# Power_Management.net
KiCad netlist of a schematic drawn in Altium Designer
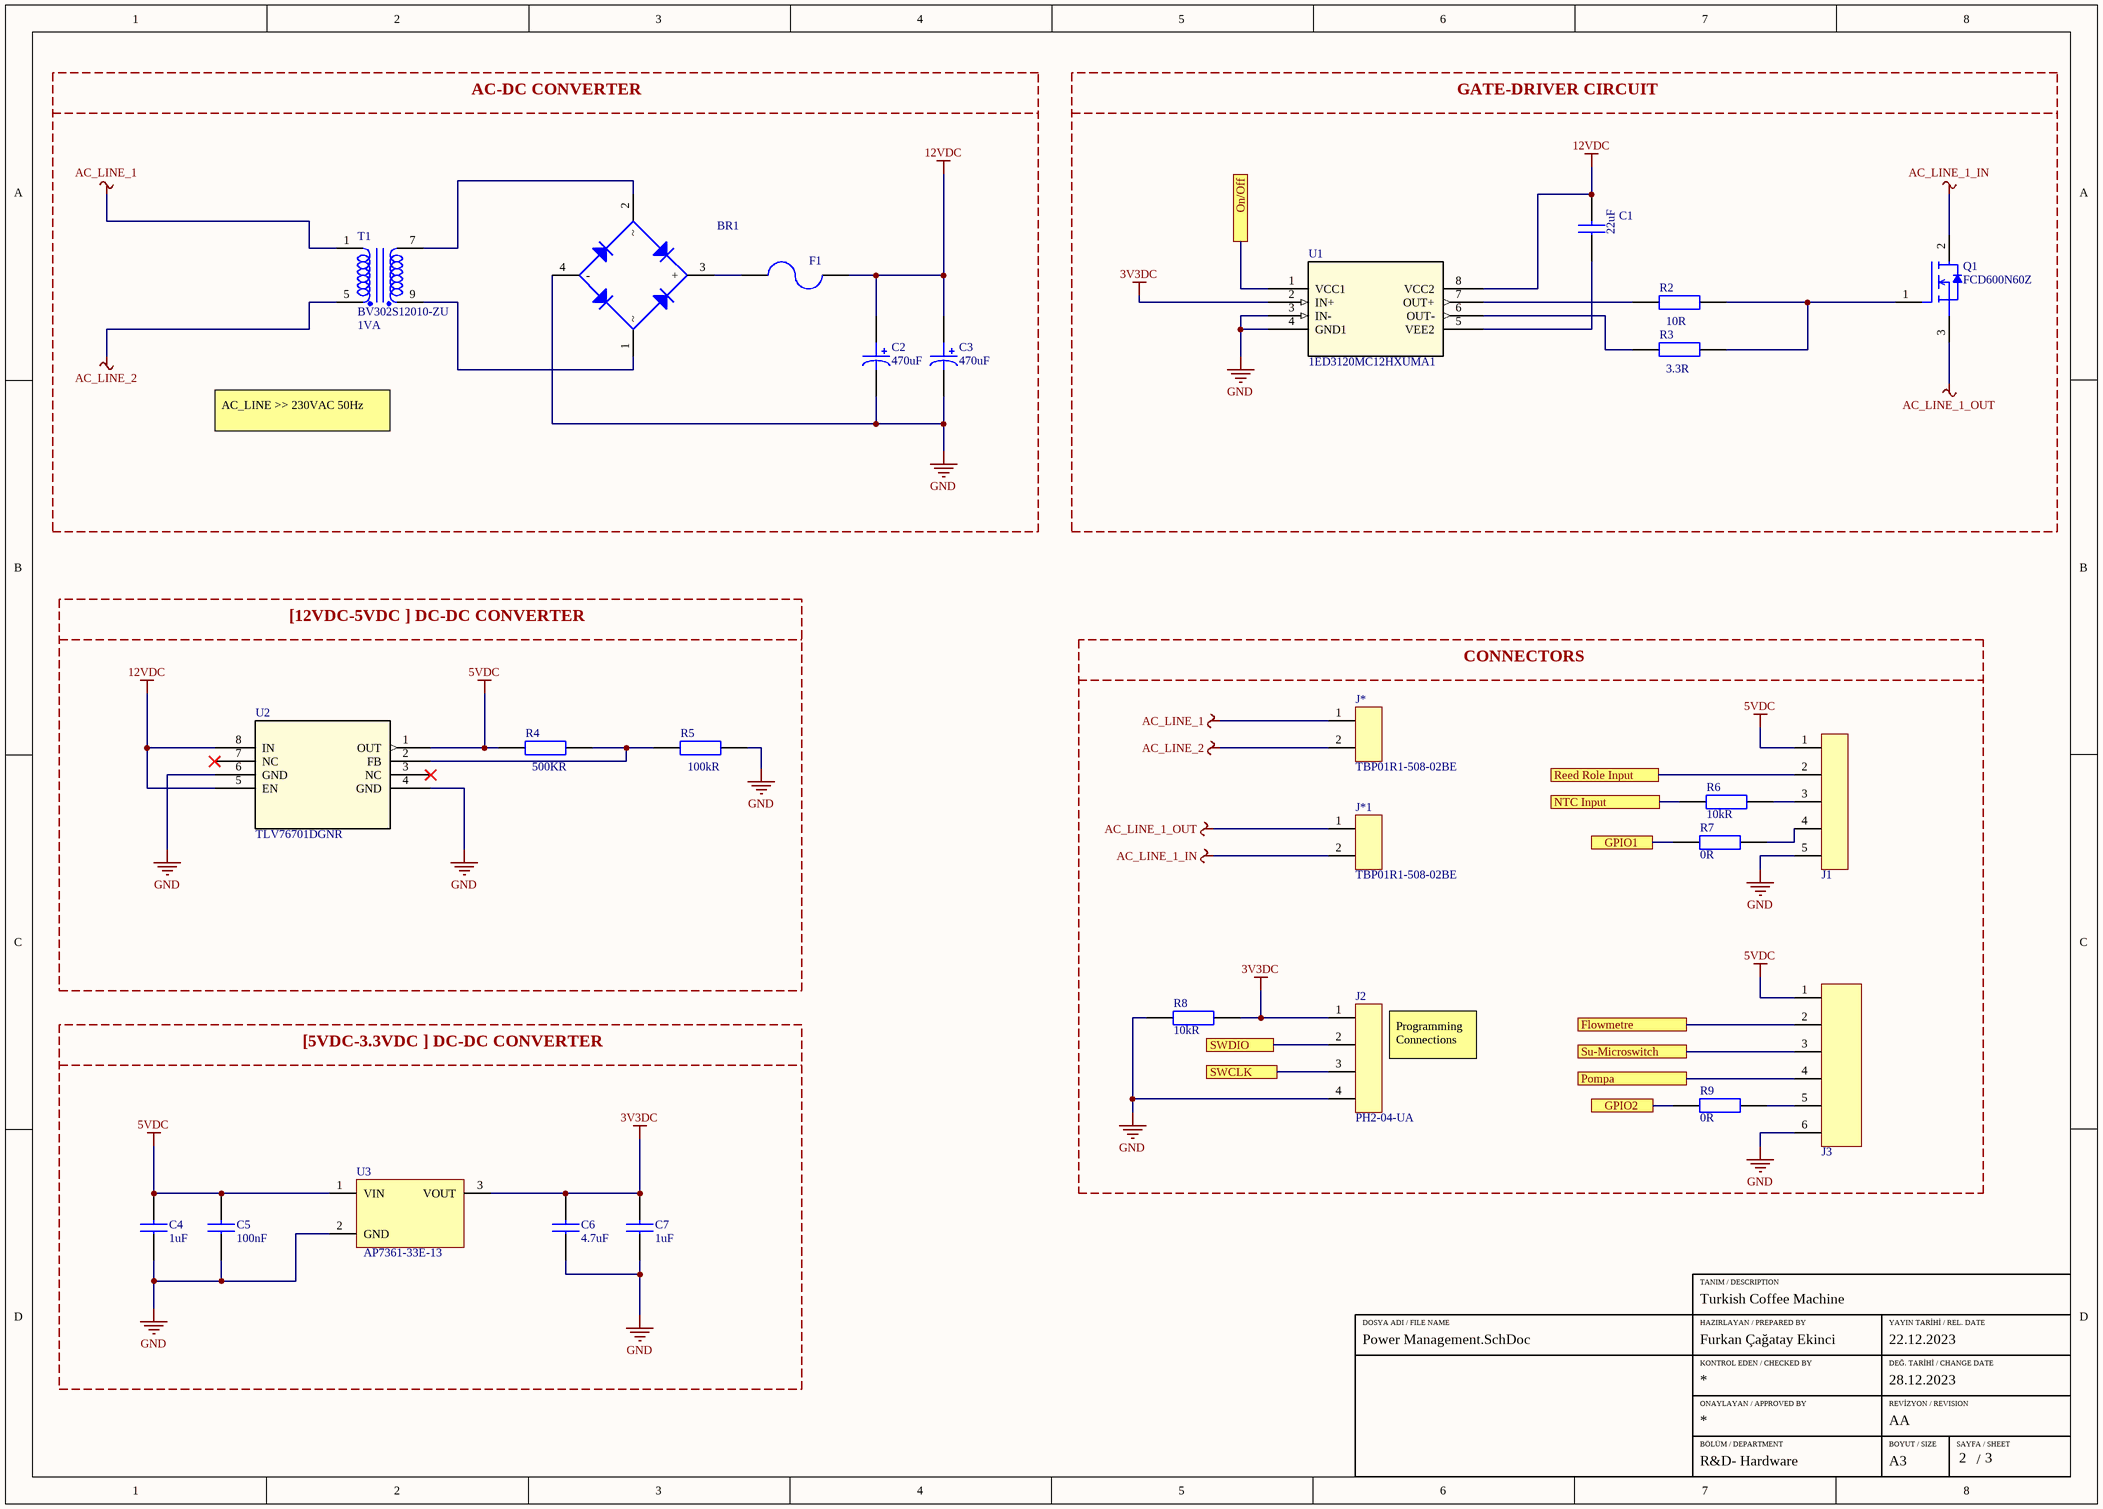
[diagram p0: Power Management.SchDoc]

(export (version "E")
  (design (tool "Eeschema 10.0.6"))
  (components
    (comp (ref "BR1")
      (value "DB105STR")
      (footprint "DB105STR")
      (description "Bridge Diode AC-DC")
      (fields (field (name "MANUFACTURER") "Sangdest Microelectronics") (field (name "DESIGNED BY") "FCE"))
      (libsource (lib "Coffee Machine") (part "DB105STR"))
    )
    (comp (ref "C1")
      (value "CL10A226MO7JZNC")
      (footprint "CAP_0603")
      (description "Multilayer Ceramic Capacitor, 22 uF, 16 V, ± 20%, X5R, 0603 [1608 Metric]")
      (fields
        (field (name "MANUFACTURER") "Samsung")
        (field (name "TOLERANCE") "20%")
        (field (name "DESIGNED BY") "FCE")
      )
      (libsource (lib "Coffee Machine") (part "CAP CER 22uF 0603"))
    )
    (comp (ref "C2")
      (value "ESH477M050AH4AA")
      (footprint "CAP_RADIAL_D10_P5")
      (description "CAP ALU ELEC 470uF 50V RADIAL")
      (fields
        (field (name "MANUFACTURER") "KEMET")
        (field (name "TOLERANCE") "20%")
        (field (name "CAPACITANCE") "470uF")
        (field (name "DESIGNED BY") "FCE")
      )
      (libsource (lib "Coffee Machine") (part "CAP ALU ELEC 470uF 50V"))
    )
    (comp (ref "C3")
      (value "ESH477M050AH4AA")
      (footprint "CAP_RADIAL_D10_P5")
      (description "CAP ALU ELEC 470uF 50V RADIAL")
      (fields
        (field (name "MANUFACTURER") "KEMET")
        (field (name "TOLERANCE") "20%")
        (field (name "CAPACITANCE") "470uF")
        (field (name "DESIGNED BY") "FCE")
      )
      (libsource (lib "Coffee Machine") (part "CAP ALU ELEC 470uF 50V"))
    )
    (comp (ref "C4")
      (value "CL21B105KBFNNNE")
      (footprint "CAP_0805")
      (description "CAP CER 1uF %10 0805")
      (fields
        (field (name "MANUFACTURER") "Samsung")
        (field (name "TOLERANCE") "10%")
        (field (name "CAPACITANCE") "1uF")
        (field (name "DESIGNED BY") "FCE")
      )
      (libsource (lib "Coffee Machine") (part "CAP CER 1uF 0805"))
    )
    (comp (ref "C5")
      (value "C0603C104K5RACTU")
      (footprint "CAP_0603")
      (description "CAP CER 100nF %10 0603 SMD")
      (fields
        (field (name "MANUFACTURER") "KEMET")
        (field (name "TOLERANCE") "10%")
        (field (name "CAPACITANCE") "100nF")
        (field (name "DESIGNED BY") "FCE")
      )
      (libsource (lib "Coffee Machine") (part "CAP CER 100nF 0603"))
    )
    (comp (ref "C6")
      (value "CL21A475KAQNNNE")
      (footprint "CAP_0805")
      (description "CAP CER 4.7uF %10 0805")
      (fields
        (field (name "MANUFACTURER") "Samsung")
        (field (name "TOLERANCE") "10%")
        (field (name "CAPACITANCE") "4.7uF")
        (field (name "DESIGNED BY") "FCE")
      )
      (libsource (lib "Coffee Machine") (part "CAP CER 4.7uF 0805"))
    )
    (comp (ref "C7")
      (value "CL21B105KBFNNNE")
      (footprint "CAP_0805")
      (description "CAP CER 1uF %10 0805")
      (fields
        (field (name "MANUFACTURER") "Samsung")
        (field (name "TOLERANCE") "10%")
        (field (name "CAPACITANCE") "1uF")
        (field (name "DESIGNED BY") "FCE")
      )
      (libsource (lib "Coffee Machine") (part "CAP CER 1uF 0805"))
    )
    (comp (ref "F1")
      (value "3413.0216.22")
      (footprint "3413.0216.22")
      (description "FUSE BRD MNT 1A 32VAC 63VDC 1206")
      (fields (field (name "MANUFACTURER") "Schurter") (field (name "DESIGNED BY") "FCE"))
      (libsource (lib "Coffee Machine") (part "FUSE 3413.0216.22"))
    )
    (comp (ref "J*")
      (value "TBP01R1-508-02BE")
      (footprint "TBP01R1-508")
      (description "2~24 Poles, Pluggable, Receptacle, Horizontal, 5.08 Pitch, Terminal Block Connector")
      (fields
        (field (name "MANUFACTURER") "CUI Devices")
        (field (name "VOLTAGE") "300V")
        (field (name "DESIGNED BY") "FCE")
      )
      (libsource (lib "Coffee Machine") (part "TBP01R1-508-02BE"))
    )
    (comp (ref "J*1")
      (value "TBP01R1-508-02BE")
      (footprint "TBP01R1-508")
      (description "2~24 Poles, Pluggable, Receptacle, Horizontal, 5.08 Pitch, Terminal Block Connector")
      (fields
        (field (name "MANUFACTURER") "CUI Devices")
        (field (name "VOLTAGE") "300V")
        (field (name "DESIGNED BY") "FCE")
      )
      (libsource (lib "Coffee Machine") (part "TBP01R1-508-02BE"))
    )
    (comp (ref "J1")
      (value "SMH-105-02-L-S")
      (footprint "PINHEADER1X5_RA")
      (description ".100 C.L. HORIZONTAL SMT SOCKET")
      (fields (field (name "MANUFACTURER") "Samtec") (field (name "DESIGNED BY") "FCE"))
      (libsource (lib "Coffee Machine") (part "SMH-105-02-L-S"))
    )
    (comp (ref "J2")
      (value "PH2-04-UA")
      (footprint "BULK")
      (description "Conn Unshrouded Header HDR 4 POS 2.54mm Solder ST Thru-Hole")
      (fields (field (name "MANUFACTURER") "Adam Equipment") (field (name "DESIGNED BY") "FCE"))
      (libsource (lib "Coffee Machine") (part "PH2-04-UA"))
    )
    (comp (ref "J3")
      (value "64800611622")
      (footprint "64800611622")
      (description "1.50mm 6PIN Connector")
      (fields (field (name "MANUFACTURER") "Wurth Electronics") (field (name "DESIGNED BY") "FCE"))
      (libsource (lib "Coffee Machine") (part "64800611622_conn_6pin"))
    )
    (comp (ref "Q1")
      (value "FCD600N60Z")
      (footprint "DPAK_TO-252AA_INF")
      (description "N-Channel Power MOSFET, SUPERFET® II, FAST, 600 V, 7.4 A, 600 mΩ, DPAK")
      (fields (field (name "MANUFACTURER") "ON Semiconductor / Fairchild") (field (name "DESIGNED BY") "FCE"))
      (libsource (lib "Coffee Machine") (part "FCD600N60Z"))
    )
    (comp (ref "R2")
      (value "RC0603FR-0710RL")
      (footprint "RES_0603")
      (description "SMD Chip Resistor, 10 Ohm, ± 1%, 100 mW, 0603 [1608 Metric], Thick Film, General Purpose")
      (fields
        (field (name "MANUFACTURER") "Yageo")
        (field (name "TOLERANCE") "1%")
        (field (name "DESIGNED BY") "FCE")
      )
      (libsource (lib "Coffee Machine") (part "RES 10 OHM 0603"))
    )
    (comp (ref "R3")
      (value "RC0603JR-073R3L")
      (footprint "RES_0603")
      (description "Res Thick Film 0603 3.3 Ohm 5% 1/10W +/-200ppm/ßC Molded SMD Paper T/R")
      (fields
        (field (name "MANUFACTURER") "Yageo")
        (field (name "TOLERANCE") "5%")
        (field (name "DESIGNED BY") "FCE")
      )
      (libsource (lib "Coffee Machine") (part "RES 3.3 OHM 0603"))
    )
    (comp (ref "R4")
      (value "CRMA1206AF500KFKEF")
      (footprint "RES_1206")
      (description "Res Thick Film 1206 500K Ohm 1% 0.3W ±100ppm/C Pad SMD Automotive T/R")
      (fields
        (field (name "MANUFACTURER") "Vishay BCcomponents")
        (field (name "TOLERANCE") "1%")
        (field (name "DESIGNED BY") "FCE")
      )
      (libsource (lib "Coffee Machine") (part "RES 500K OHM 0603"))
    )
    (comp (ref "R5")
      (value "RC0603JR-07100KL")
      (footprint "RES_0603")
      (description "SMD Chip Resistor, 100 kOhm, ± 5%, 100 mW, 0603 [1608 Metric], Thick Film, General Purpose")
      (fields
        (field (name "MANUFACTURER") "Yageo")
        (field (name "TOLERANCE") "5%")
        (field (name "DESIGNED BY") "FCE")
      )
      (libsource (lib "Coffee Machine") (part "RES 100K OHM 0603"))
    )
    (comp (ref "R6")
      (value "RC0603FR-0710KL")
      (footprint "RES_0603")
      (description "RES 10K %1 OHM 0603 SMD")
      (fields
        (field (name "MANUFACTURER") "Yageo")
        (field (name "TOLERANCE") "1%")
        (field (name "RESISTANCE") "10kR")
        (field (name "DESIGNED BY") "FCE")
      )
      (libsource (lib "Coffee Machine") (part "RES 10K OHM 0603"))
    )
    (comp (ref "R7")
      (value "RC0603JR-070RL")
      (footprint "RES_0603")
      (description "RES 0 %1 OHM 0603 SMD")
      (fields
        (field (name "MANUFACTURER") "Yageo")
        (field (name "TOLERANCE") "1%")
        (field (name "RESISTANCE") "0R")
        (field (name "DESIGNED BY") "FCE")
      )
      (libsource (lib "Coffee Machine") (part "RES 0 OHM 0603"))
    )
    (comp (ref "R8")
      (value "RC0603FR-0710KL")
      (footprint "RES_0603")
      (description "RES 10K %1 OHM 0603 SMD")
      (fields
        (field (name "MANUFACTURER") "Yageo")
        (field (name "TOLERANCE") "1%")
        (field (name "RESISTANCE") "10kR")
        (field (name "DESIGNED BY") "FCE")
      )
      (libsource (lib "Coffee Machine") (part "RES 10K OHM 0603"))
    )
    (comp (ref "R9")
      (value "RC0603JR-070RL")
      (footprint "RES_0603")
      (description "RES 0 %1 OHM 0603 SMD")
      (fields
        (field (name "MANUFACTURER") "Yageo")
        (field (name "TOLERANCE") "1%")
        (field (name "RESISTANCE") "0R")
        (field (name "DESIGNED BY") "FCE")
      )
      (libsource (lib "Coffee Machine") (part "RES 0 OHM 0603"))
    )
    (comp (ref "T1")
      (value "BV302S12010-ZU")
      (footprint "BV302S")
      (description "230-12 Transformer 1VA")
      (fields
        (field (name "MANUFACTURER") "Zettler Magnetics")
        (field (name "RATED POWER") "1VA")
        (field (name "DESIGNED BY") "FCE")
      )
      (libsource (lib "Coffee Machine") (part "BV302S12010-ZU"))
    )
    (comp (ref "U1")
      (value "1ED3120MC12HXUMA1")
      (footprint "SOIC8")
      (description "IGBT & MOSFET Gate Driver 5.5A 1-OUT Hi Side Non-Inv/Inv 8-Pin DSO T/R")
      (fields (field (name "MANUFACTURER") "Infineon") (field (name "DESIGNED BY") "FCE"))
      (libsource (lib "Coffee Machine") (part "1ED3120MC12HXUMA1"))
    )
    (comp (ref "U2")
      (value "TLV76701DGNR")
      (footprint "PG-DSO-8-66")
      (fields (field (name "MANUFACTURER") "Texas Instruments") (field (name "DESIGNED BY") "FCE"))
      (libsource (lib "Coffee Machine") (part "TLV76701DGNR"))
    )
    (comp (ref "U3")
      (value "AP7361-33E-13")
      (footprint "SOT223")
      (description "LDO Regulator Pos 3.3V 1A 4-Pin(3+Tab) SOT-223 T/R")
      (fields (field (name "MANUFACTURER") "Diodes") (field (name "DESIGNED BY") "FCE"))
      (libsource (lib "Coffee Machine") (part "AP7361-33E-13"))
    )
  )
  (nets
    (net (code "1") (name "/Flowmetre") (class "Default") (node (ref "J3") (pin "2") (pintype "power_in")))
    (net (code "2") (name "/GPIO1") (class "Default")
      (node (ref "R7") (pin "1") (pinfunction "1_1") (pintype "passive"))
    )
    (net (code "3") (name "/GPIO2") (class "Default")
      (node (ref "R9") (pin "1") (pinfunction "1_1") (pintype "passive"))
    )
    (net (code "4") (name "/NTC Input") (class "Default")
      (node (ref "R6") (pin "1") (pinfunction "1_1") (pintype "passive"))
    )
    (net (code "5") (name "/On{slash}Off") (class "Default")
      (node (ref "U1") (pin "1") (pinfunction "VCC1_1") (pintype "power_in"))
    )
    (net (code "6") (name "/Pompa") (class "Default") (node (ref "J3") (pin "4") (pintype "power_in")))
    (net (code "7") (name "/Reed Role Input") (class "Default")
      (node (ref "J1") (pin "2") (pinfunction "2_2") (pintype "power_in"))
    )
    (net (code "8") (name "/SWCLK") (class "Default")
      (node (ref "J2") (pin "3") (pinfunction "3_3") (pintype "power_in"))
    )
    (net (code "9") (name "/SWDIO") (class "Default")
      (node (ref "J2") (pin "2") (pinfunction "2_2") (pintype "power_in"))
    )
    (net (code "10") (name "/Su-Microswitch") (class "Default")
      (node (ref "J3") (pin "3") (pintype "power_in"))
    )
    (net (code "11") (name "3V3DC") (class "Default")
      (node (ref "C6") (pin "2") (pinfunction "2_2") (pintype "passive"))
      (node (ref "C7") (pin "2") (pinfunction "2_2") (pintype "passive"))
      (node (ref "J2") (pin "1") (pinfunction "1_1") (pintype "power_in"))
      (node (ref "R8") (pin "2") (pinfunction "2_2") (pintype "passive"))
      (node (ref "U1") (pin "2") (pinfunction "IN+_2") (pintype "input"))
      (node (ref "U3") (pin "3") (pinfunction "VOUT_3") (pintype "passive"))
    )
    (net (code "12") (name "5VDC") (class "Default")
      (node (ref "C4") (pin "2") (pinfunction "2_2") (pintype "passive"))
      (node (ref "C5") (pin "2") (pinfunction "2_2") (pintype "passive"))
      (node (ref "J1") (pin "1") (pinfunction "1_1") (pintype "power_in"))
      (node (ref "J3") (pin "1") (pintype "power_in"))
      (node (ref "R4") (pin "1") (pinfunction "1_1") (pintype "passive"))
      (node (ref "U2") (pin "1") (pinfunction "OUT_1") (pintype "output"))
      (node (ref "U3") (pin "1") (pinfunction "VIN_1") (pintype "passive"))
    )
    (net (code "13") (name "12VDC") (class "Default")
      (node (ref "C1") (pin "2") (pinfunction "2_2") (pintype "passive"))
      (node (ref "C2") (pin "1") (pinfunction "1_1") (pintype "passive"))
      (node (ref "C3") (pin "1") (pinfunction "1_1") (pintype "passive"))
      (node (ref "F1") (pin "2") (pinfunction "2_2") (pintype "passive"))
      (node (ref "U1") (pin "8") (pinfunction "VCC2_8") (pintype "power_in"))
      (node (ref "U2") (pin "5") (pinfunction "EN_5") (pintype "passive"))
      (node (ref "U2") (pin "8") (pinfunction "IN_8") (pintype "passive"))
    )
    (net (code "14") (name "AC_LINE_1") (class "Default")
      (node (ref "J*") (pin "1") (pinfunction "1_1") (pintype "power_in"))
      (node (ref "T1") (pin "1") (pinfunction "1_1") (pintype "passive"))
    )
    (net (code "15") (name "AC_LINE_1_IN") (class "Default")
      (node (ref "J*1") (pin "2") (pinfunction "2_2") (pintype "power_in"))
      (node (ref "Q1") (pin "2") (pinfunction "D_2") (pintype "passive"))
    )
    (net (code "16") (name "AC_LINE_1_OUT") (class "Default")
      (node (ref "J*1") (pin "1") (pinfunction "1_1") (pintype "power_in"))
      (node (ref "Q1") (pin "3") (pinfunction "S_3") (pintype "passive"))
    )
    (net (code "17") (name "AC_LINE_2") (class "Default")
      (node (ref "J*") (pin "2") (pinfunction "2_2") (pintype "power_in"))
      (node (ref "T1") (pin "5") (pinfunction "5_5") (pintype "passive"))
    )
    (net (code "18") (name "GND") (class "Default")
      (node (ref "BR1") (pin "4") (pinfunction "-_4") (pintype "passive"))
      (node (ref "C2") (pin "2") (pinfunction "2_2") (pintype "passive"))
      (node (ref "C3") (pin "2") (pinfunction "2_2") (pintype "passive"))
      (node (ref "C4") (pin "1") (pinfunction "1_1") (pintype "passive"))
      (node (ref "C5") (pin "1") (pinfunction "1_1") (pintype "passive"))
      (node (ref "C6") (pin "1") (pinfunction "1_1") (pintype "passive"))
      (node (ref "C7") (pin "1") (pinfunction "1_1") (pintype "passive"))
      (node (ref "J1") (pin "5") (pinfunction "5_5") (pintype "power_in"))
      (node (ref "J2") (pin "4") (pinfunction "4_4") (pintype "power_in"))
      (node (ref "J3") (pin "6") (pintype "power_in"))
      (node (ref "R5") (pin "2") (pinfunction "2_2") (pintype "passive"))
      (node (ref "R8") (pin "1") (pinfunction "1_1") (pintype "passive"))
      (node (ref "U1") (pin "3") (pinfunction "IN-_3") (pintype "input"))
      (node (ref "U1") (pin "4") (pinfunction "GND1_4") (pintype "power_in"))
      (node (ref "U2") (pin "4") (pinfunction "GND_4") (pintype "power_in"))
      (node (ref "U2") (pin "6") (pinfunction "GND_6") (pintype "power_in"))
      (node (ref "U3") (pin "2") (pinfunction "GND_2") (pintype "passive"))
    )
    (net (code "19") (name "Net-(BR1-+)") (class "Default")
      (node (ref "BR1") (pin "3") (pinfunction "+_3") (pintype "passive"))
      (node (ref "F1") (pin "1") (pinfunction "1_1") (pintype "passive"))
    )
    (net (code "20") (name "Net-(BR1-~-Pad1)") (class "Default")
      (node (ref "BR1") (pin "1") (pinfunction "~_1") (pintype "passive"))
      (node (ref "T1") (pin "9") (pinfunction "9_9") (pintype "passive"))
    )
    (net (code "21") (name "Net-(BR1-~-Pad2)") (class "Default")
      (node (ref "BR1") (pin "2") (pinfunction "~_2") (pintype "passive"))
      (node (ref "T1") (pin "7") (pinfunction "7_7") (pintype "passive"))
    )
    (net (code "22") (name "Net-(J1-Pad3)") (class "Default")
      (node (ref "J1") (pin "3") (pinfunction "3_3") (pintype "power_in"))
      (node (ref "R6") (pin "2") (pinfunction "2_2") (pintype "passive"))
    )
    (net (code "23") (name "Net-(J1-Pad4)") (class "Default")
      (node (ref "J1") (pin "4") (pinfunction "4_4") (pintype "power_in"))
      (node (ref "R7") (pin "2") (pinfunction "2_2") (pintype "passive"))
    )
    (net (code "24") (name "Net-(J3-Pad5)") (class "Default")
      (node (ref "J3") (pin "5") (pintype "power_in"))
      (node (ref "R9") (pin "2") (pinfunction "2_2") (pintype "passive"))
    )
    (net (code "25") (name "Net-(Q1-G)") (class "Default")
      (node (ref "Q1") (pin "1") (pinfunction "G_1") (pintype "passive"))
      (node (ref "R2") (pin "2") (pinfunction "2_2") (pintype "passive"))
      (node (ref "R3") (pin "2") (pinfunction "2_2") (pintype "passive"))
    )
    (net (code "26") (name "Net-(U1-OUT+)") (class "Default")
      (node (ref "R2") (pin "1") (pinfunction "1_1") (pintype "passive"))
      (node (ref "U1") (pin "7") (pinfunction "OUT+_7") (pintype "output"))
    )
    (net (code "27") (name "Net-(U1-OUT-)") (class "Default")
      (node (ref "R3") (pin "1") (pinfunction "1_1") (pintype "passive"))
      (node (ref "U1") (pin "6") (pinfunction "OUT-_6") (pintype "output"))
    )
    (net (code "28") (name "Net-(U1-VEE2)") (class "Default")
      (node (ref "C1") (pin "1") (pinfunction "1_1") (pintype "passive"))
      (node (ref "U1") (pin "5") (pinfunction "VEE2_5") (pintype "power_in"))
    )
    (net (code "29") (name "Net-(U2-FB)") (class "Default")
      (node (ref "R4") (pin "2") (pinfunction "2_2") (pintype "passive"))
      (node (ref "R5") (pin "1") (pinfunction "1_1") (pintype "passive"))
      (node (ref "U2") (pin "2") (pinfunction "FB_2") (pintype "passive"))
    )
    (net (code "30") (name "unconnected-(U2-NC-Pad3)") (class "Default")
      (node (ref "U2") (pin "3") (pinfunction "NC_3") (pintype "passive+no_connect"))
    )
    (net (code "31") (name "unconnected-(U2-NC-Pad7)") (class "Default")
      (node (ref "U2") (pin "7") (pinfunction "NC_7") (pintype "passive+no_connect"))
    )
  )
)
